# schematic.net
KiCad netlist of a schematic drawn in EasyEDA
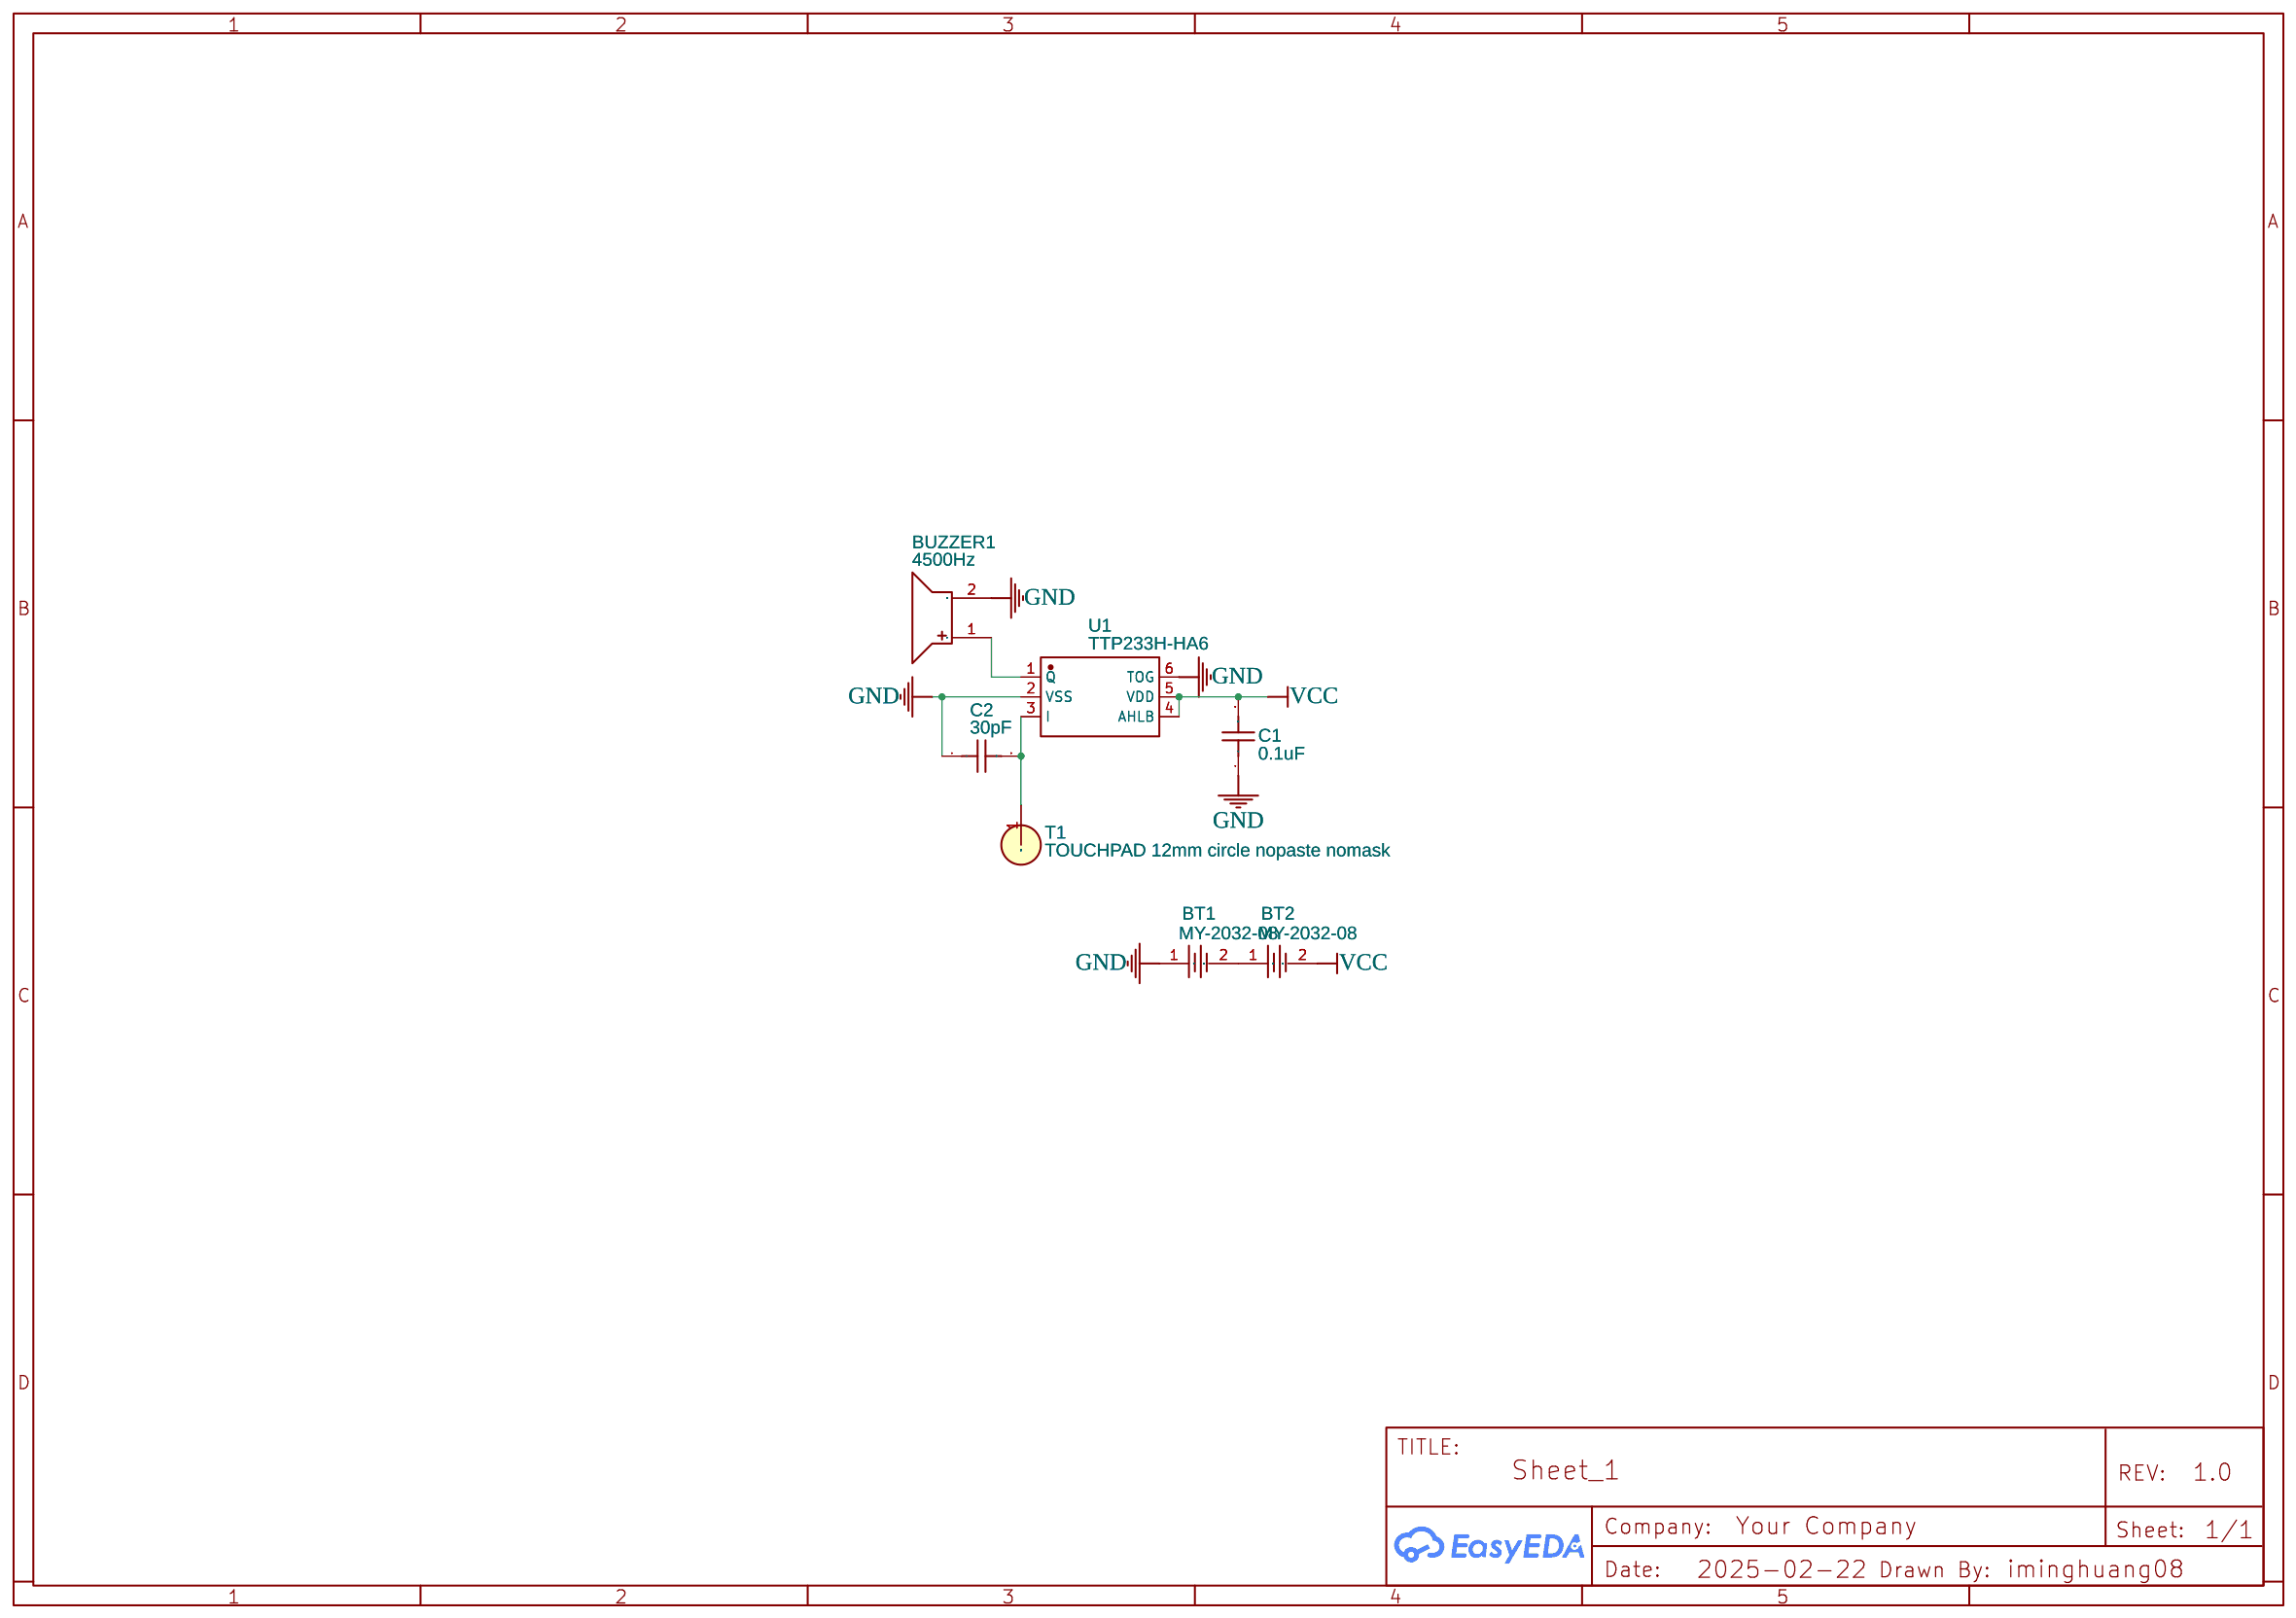
[diagram p0: schematic sheet]

(export (version "E")
  (design (tool "Eeschema 10.0.6"))
  (components
    (comp (ref "BT1")
      (value "MY-2032-08")
      (fields (field (name "Manufacturer") "MYOUNG(美阳)"))
      (libsource (lib "") (part "MY-2032-08"))
    )
    (comp (ref "BT2")
      (value "MY-2032-08")
      (fields (field (name "Manufacturer") "MYOUNG(美阳)"))
      (libsource (lib "") (part "MY-2032-08"))
    )
    (comp (ref "BUZZER1")
      (value "4500Hz")
      (fields (field (name "Manufacturer Part") "HND-1407B") (field (name "Manufacturer") "华能"))
      (libsource (lib "") (part "HND-1407B"))
    )
    (comp (ref "C1") (value "0.1uF") (libsource (lib "") (part "C_0603_US")))
    (comp (ref "C2") (value "30pF") (libsource (lib "") (part "C_0603_US_1")))
    (comp (ref "T1")
      (value "TOUCHPAD 12mm circle nopaste nomask")
      (libsource (lib "") (part "TOUCHPAD 12mm circle nopaste nomask"))
    )
    (comp (ref "U1")
      (value "TTP233H-HA6")
      (fields (field (name "Manufacturer") "TONTEK(通泰)"))
      (libsource (lib "") (part "TTP233H-HA6"))
    )
  )
  (nets
    (net (code "1") (name "GND") (class "Default")
      (node (ref "BT1") (pin "1") (pinfunction "1_1") (pintype "input"))
      (node (ref "BUZZER1") (pin "2") (pinfunction "2_2") (pintype "unspecified"))
      (node (ref "C1") (pin "1") (pinfunction "1_1") (pintype "unspecified"))
      (node (ref "C2") (pin "1") (pinfunction "1_1") (pintype "unspecified"))
      (node (ref "U1") (pin "2") (pinfunction "VSS_2") (pintype "unspecified"))
      (node (ref "U1") (pin "6") (pinfunction "TOG_6") (pintype "unspecified"))
    )
    (net (code "2") (name "Net-(BT1-Pad2)") (class "Default")
      (node (ref "BT1") (pin "2") (pinfunction "2_2") (pintype "input"))
      (node (ref "BT2") (pin "1") (pinfunction "1_1") (pintype "input"))
    )
    (net (code "3") (name "Net-(T1-Touch)") (class "Default")
      (node (ref "C2") (pin "2") (pinfunction "2_2") (pintype "unspecified"))
      (node (ref "T1") (pin "1") (pinfunction "Touch_1") (pintype "unspecified"))
      (node (ref "U1") (pin "3") (pinfunction "I_3") (pintype "unspecified"))
    )
    (net (code "4") (name "Net-(U1-Q)") (class "Default")
      (node (ref "BUZZER1") (pin "1") (pinfunction "1_1") (pintype "unspecified"))
      (node (ref "U1") (pin "1") (pinfunction "Q_1") (pintype "unspecified"))
    )
    (net (code "5") (name "VCC") (class "Default")
      (node (ref "BT2") (pin "2") (pinfunction "2_2") (pintype "input"))
      (node (ref "C1") (pin "2") (pinfunction "2_2") (pintype "unspecified"))
      (node (ref "U1") (pin "4") (pinfunction "AHLB_4") (pintype "unspecified"))
      (node (ref "U1") (pin "5") (pinfunction "VDD_5") (pintype "unspecified"))
    )
  )
)
